# M217A.net
KiCad netlist of a schematic drawn in EAGLE
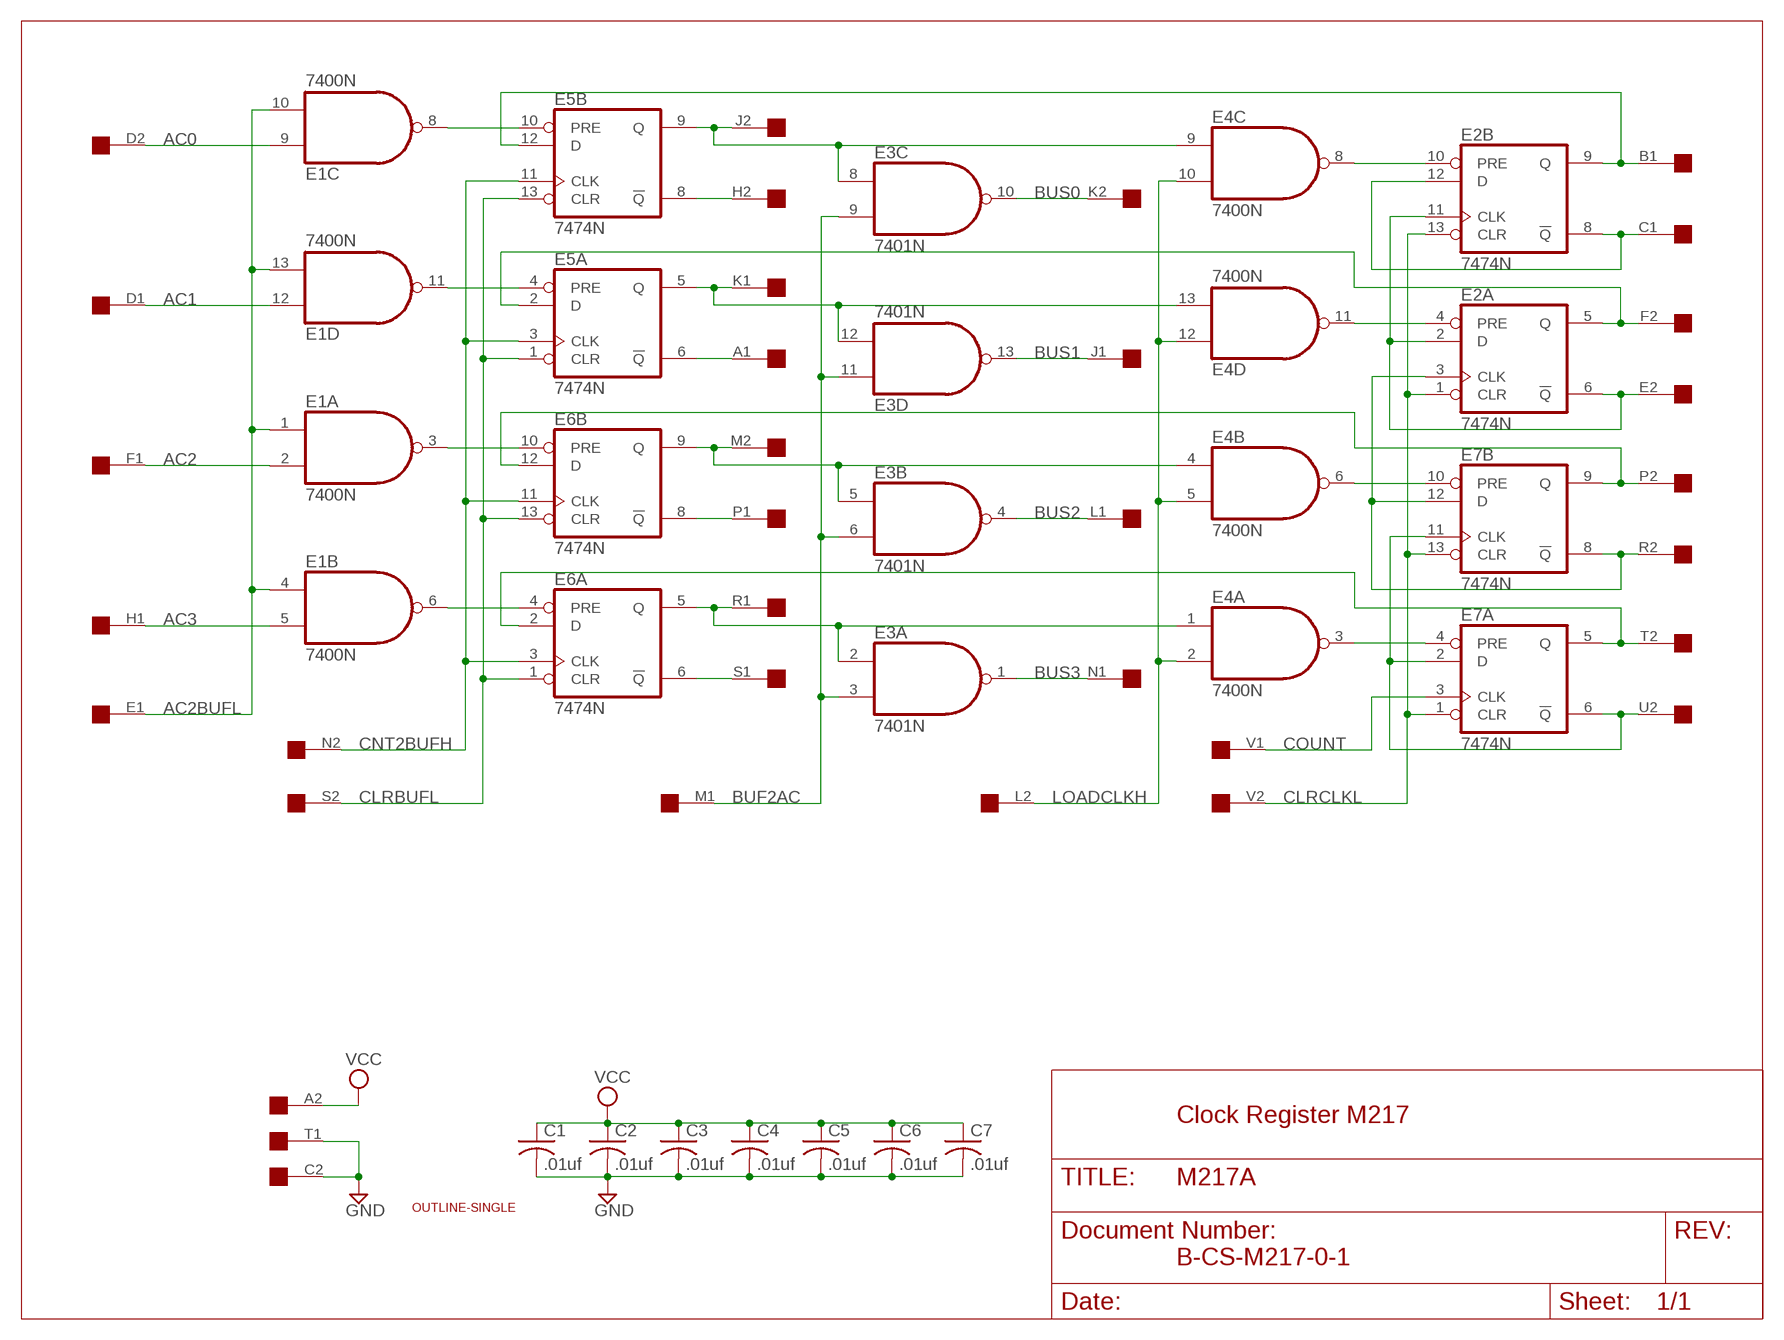
[diagram p0: schematic, sheet 1]

(export (version "E")
  (design (tool "Eeschema 10.0.6"))
  (components
    (comp (ref "C1")
      (value ".01uf")
      (footprint "eagle-import:C050-025X075")
      (libsource (lib "eagle-import") (part "C-US050-025X075"))
    )
    (comp (ref "C2")
      (value ".01uf")
      (footprint "eagle-import:C050-025X075")
      (libsource (lib "eagle-import") (part "C-US050-025X075"))
    )
    (comp (ref "C3")
      (value ".01uf")
      (footprint "eagle-import:C050-025X075")
      (libsource (lib "eagle-import") (part "C-US050-025X075"))
    )
    (comp (ref "C4")
      (value ".01uf")
      (footprint "eagle-import:C050-025X075")
      (libsource (lib "eagle-import") (part "C-US050-025X075"))
    )
    (comp (ref "C5")
      (value ".01uf")
      (footprint "eagle-import:C050-025X075")
      (libsource (lib "eagle-import") (part "C-US050-025X075"))
    )
    (comp (ref "C6")
      (value ".01uf")
      (footprint "eagle-import:C050-025X075")
      (libsource (lib "eagle-import") (part "C-US050-025X075"))
    )
    (comp (ref "C7")
      (value ".01uf")
      (footprint "eagle-import:C050-025X075")
      (libsource (lib "eagle-import") (part "C-US050-025X075"))
    )
    (comp (ref "E1")
      (value "7400N")
      (footprint "eagle-import:DIL14")
      (libsource (lib "eagle-import") (part "7400N"))
    )
    (comp (ref "E2")
      (value "7474N")
      (footprint "eagle-import:DIL14")
      (libsource (lib "eagle-import") (part "7474NS"))
    )
    (comp (ref "E3")
      (value "7401N")
      (footprint "eagle-import:DIL14")
      (libsource (lib "eagle-import") (part "7401NLS"))
    )
    (comp (ref "E4")
      (value "7400N")
      (footprint "eagle-import:DIL14")
      (libsource (lib "eagle-import") (part "7400N"))
    )
    (comp (ref "E5")
      (value "7474N")
      (footprint "eagle-import:DIL14")
      (libsource (lib "eagle-import") (part "7474NS"))
    )
    (comp (ref "E6")
      (value "7474N")
      (footprint "eagle-import:DIL14")
      (libsource (lib "eagle-import") (part "7474NS"))
    )
    (comp (ref "E7")
      (value "7474N")
      (footprint "eagle-import:DIL14")
      (libsource (lib "eagle-import") (part "7474NS"))
    )
    (comp (ref "U$1")
      (value "OUTLINE-SINGLE")
      (footprint "eagle-import:SINGLE")
      (libsource (lib "eagle-import") (part "OUTLINE-SINGLE"))
    )
    (comp (ref "U$4")
      (value "SINGLE")
      (footprint "eagle-import:EDGE-CON2")
      (libsource (lib "eagle-import") (part "SINGLE"))
    )
  )
  (nets
    (net (code "1") (name "/AC0") (class "Default")
      (node (ref "E1") (pin "9") (pinfunction "I0_9") (pintype "input"))
      (node (ref "U$4") (pin "D2") (pinfunction "1_D2") (pintype "bidirectional"))
    )
    (net (code "2") (name "/AC1") (class "Default")
      (node (ref "E1") (pin "12") (pinfunction "I0_12") (pintype "input"))
      (node (ref "U$4") (pin "D1") (pinfunction "1_D1") (pintype "bidirectional"))
    )
    (net (code "3") (name "/AC2") (class "Default")
      (node (ref "E1") (pin "2") (pinfunction "I1_2") (pintype "input"))
      (node (ref "U$4") (pin "F1") (pinfunction "1_F1") (pintype "bidirectional"))
    )
    (net (code "4") (name "/AC2BUFL") (class "Default")
      (node (ref "E1") (pin "1") (pinfunction "I0_1") (pintype "input"))
      (node (ref "E1") (pin "10") (pinfunction "I1_10") (pintype "input"))
      (node (ref "E1") (pin "13") (pinfunction "I1_13") (pintype "input"))
      (node (ref "E1") (pin "4") (pinfunction "I0_4") (pintype "input"))
      (node (ref "U$4") (pin "E1") (pinfunction "1_E1") (pintype "bidirectional"))
    )
    (net (code "5") (name "/AC3") (class "Default")
      (node (ref "E1") (pin "5") (pinfunction "I1_5") (pintype "input"))
      (node (ref "U$4") (pin "H1") (pinfunction "1_H1") (pintype "bidirectional"))
    )
    (net (code "6") (name "/BUF2AC") (class "Default")
      (node (ref "E3") (pin "11") (pinfunction "I0_11") (pintype "input"))
      (node (ref "E3") (pin "3") (pinfunction "I1_3") (pintype "input"))
      (node (ref "E3") (pin "6") (pinfunction "I1_6") (pintype "input"))
      (node (ref "E3") (pin "9") (pinfunction "I1_9") (pintype "input"))
      (node (ref "U$4") (pin "M1") (pinfunction "1_M1") (pintype "bidirectional"))
    )
    (net (code "7") (name "/BUS0") (class "Default")
      (node (ref "E3") (pin "10") (pinfunction "O_10") (pintype "open_collector"))
      (node (ref "U$4") (pin "K2") (pinfunction "1_K2") (pintype "bidirectional"))
    )
    (net (code "8") (name "/BUS1") (class "Default")
      (node (ref "E3") (pin "13") (pinfunction "O_13") (pintype "open_collector"))
      (node (ref "U$4") (pin "J1") (pinfunction "1_J1") (pintype "bidirectional"))
    )
    (net (code "9") (name "/BUS2") (class "Default")
      (node (ref "E3") (pin "4") (pinfunction "O_4") (pintype "open_collector"))
      (node (ref "U$4") (pin "L1") (pinfunction "1_L1") (pintype "bidirectional"))
    )
    (net (code "10") (name "/BUS3") (class "Default")
      (node (ref "E3") (pin "1") (pinfunction "O_1") (pintype "open_collector"))
      (node (ref "U$4") (pin "N1") (pinfunction "1_N1") (pintype "bidirectional"))
    )
    (net (code "11") (name "/CLRBUFL") (class "Default")
      (node (ref "E5") (pin "1") (pinfunction "CLR_1") (pintype "input"))
      (node (ref "E5") (pin "13") (pinfunction "CLR_13") (pintype "input"))
      (node (ref "E6") (pin "1") (pinfunction "CLR_1") (pintype "input"))
      (node (ref "E6") (pin "13") (pinfunction "CLR_13") (pintype "input"))
      (node (ref "U$4") (pin "S2") (pinfunction "1_S2") (pintype "bidirectional"))
    )
    (net (code "12") (name "/CLRCLKL") (class "Default")
      (node (ref "E2") (pin "1") (pinfunction "CLR_1") (pintype "input"))
      (node (ref "E2") (pin "13") (pinfunction "CLR_13") (pintype "input"))
      (node (ref "E7") (pin "1") (pinfunction "CLR_1") (pintype "input"))
      (node (ref "E7") (pin "13") (pinfunction "CLR_13") (pintype "input"))
      (node (ref "U$4") (pin "V2") (pinfunction "1_V2") (pintype "bidirectional"))
    )
    (net (code "13") (name "/CNT2BUFH") (class "Default")
      (node (ref "E5") (pin "11") (pinfunction "CLK_11") (pintype "input"))
      (node (ref "E5") (pin "3") (pinfunction "CLK_3") (pintype "input"))
      (node (ref "E6") (pin "11") (pinfunction "CLK_11") (pintype "input"))
      (node (ref "E6") (pin "3") (pinfunction "CLK_3") (pintype "input"))
      (node (ref "U$4") (pin "N2") (pinfunction "1_N2") (pintype "bidirectional"))
    )
    (net (code "14") (name "/COUNT") (class "Default")
      (node (ref "E7") (pin "3") (pinfunction "CLK_3") (pintype "input"))
      (node (ref "U$4") (pin "V1") (pinfunction "1_V1") (pintype "bidirectional"))
    )
    (net (code "15") (name "/LOADCLKH") (class "Default")
      (node (ref "E4") (pin "10") (pinfunction "I1_10") (pintype "input"))
      (node (ref "E4") (pin "12") (pinfunction "I0_12") (pintype "input"))
      (node (ref "E4") (pin "2") (pinfunction "I1_2") (pintype "input"))
      (node (ref "E4") (pin "5") (pinfunction "I1_5") (pintype "input"))
      (node (ref "U$4") (pin "L2") (pinfunction "1_L2") (pintype "bidirectional"))
    )
    (net (code "16") (name "GND") (class "Default")
      (node (ref "C1") (pin "2") (pinfunction "2_2") (pintype "passive"))
      (node (ref "C2") (pin "2") (pinfunction "2_2") (pintype "passive"))
      (node (ref "C3") (pin "2") (pinfunction "2_2") (pintype "passive"))
      (node (ref "C4") (pin "2") (pinfunction "2_2") (pintype "passive"))
      (node (ref "C5") (pin "2") (pinfunction "2_2") (pintype "passive"))
      (node (ref "C6") (pin "2") (pinfunction "2_2") (pintype "passive"))
      (node (ref "C7") (pin "2") (pinfunction "2_2") (pintype "passive"))
      (node (ref "U$4") (pin "C2") (pinfunction "1_C2") (pintype "bidirectional"))
      (node (ref "U$4") (pin "T1") (pinfunction "1_T1") (pintype "bidirectional"))
    )
    (net (code "17") (name "Net-(E1A-O)") (class "Default")
      (node (ref "E1") (pin "3") (pinfunction "O_3") (pintype "output"))
      (node (ref "E6") (pin "10") (pinfunction "PRE_10") (pintype "input"))
    )
    (net (code "18") (name "Net-(E1B-O)") (class "Default")
      (node (ref "E1") (pin "6") (pinfunction "O_6") (pintype "output"))
      (node (ref "E6") (pin "4") (pinfunction "PRE_4") (pintype "input"))
    )
    (net (code "19") (name "Net-(E1C-O)") (class "Default")
      (node (ref "E1") (pin "8") (pinfunction "O_8") (pintype "output"))
      (node (ref "E5") (pin "10") (pinfunction "PRE_10") (pintype "input"))
    )
    (net (code "20") (name "Net-(E1D-O)") (class "Default")
      (node (ref "E1") (pin "11") (pinfunction "O_11") (pintype "output"))
      (node (ref "E5") (pin "4") (pinfunction "PRE_4") (pintype "input"))
    )
    (net (code "21") (name "Net-(E2A-CLK)") (class "Default")
      (node (ref "E2") (pin "3") (pinfunction "CLK_3") (pintype "input"))
      (node (ref "E7") (pin "12") (pinfunction "D_12") (pintype "input"))
      (node (ref "E7") (pin "8") (pinfunction "~{Q}_8") (pintype "output"))
      (node (ref "U$4") (pin "R2") (pinfunction "1_R2") (pintype "bidirectional"))
    )
    (net (code "22") (name "Net-(E2A-D)") (class "Default")
      (node (ref "E2") (pin "11") (pinfunction "CLK_11") (pintype "input"))
      (node (ref "E2") (pin "2") (pinfunction "D_2") (pintype "input"))
      (node (ref "E2") (pin "6") (pinfunction "~{Q}_6") (pintype "output"))
      (node (ref "U$4") (pin "E2") (pinfunction "1_E2") (pintype "bidirectional"))
    )
    (net (code "23") (name "Net-(E2A-PRE)") (class "Default")
      (node (ref "E2") (pin "4") (pinfunction "PRE_4") (pintype "input"))
      (node (ref "E4") (pin "11") (pinfunction "O_11") (pintype "output"))
    )
    (net (code "24") (name "Net-(E2A-Q)") (class "Default")
      (node (ref "E2") (pin "5") (pinfunction "Q_5") (pintype "output"))
      (node (ref "E5") (pin "2") (pinfunction "D_2") (pintype "input"))
      (node (ref "U$4") (pin "F2") (pinfunction "1_F2") (pintype "bidirectional"))
    )
    (net (code "25") (name "Net-(E2B-D)") (class "Default")
      (node (ref "E2") (pin "12") (pinfunction "D_12") (pintype "input"))
      (node (ref "E2") (pin "8") (pinfunction "~{Q}_8") (pintype "output"))
      (node (ref "U$4") (pin "C1") (pinfunction "1_C1") (pintype "bidirectional"))
    )
    (net (code "26") (name "Net-(E2B-PRE)") (class "Default")
      (node (ref "E2") (pin "10") (pinfunction "PRE_10") (pintype "input"))
      (node (ref "E4") (pin "8") (pinfunction "O_8") (pintype "output"))
    )
    (net (code "27") (name "Net-(E2B-Q)") (class "Default")
      (node (ref "E2") (pin "9") (pinfunction "Q_9") (pintype "output"))
      (node (ref "E5") (pin "12") (pinfunction "D_12") (pintype "input"))
      (node (ref "U$4") (pin "B1") (pinfunction "1_B1") (pintype "bidirectional"))
    )
    (net (code "28") (name "Net-(E3A-I0)") (class "Default")
      (node (ref "E3") (pin "2") (pinfunction "I0_2") (pintype "input"))
      (node (ref "E4") (pin "1") (pinfunction "I0_1") (pintype "input"))
      (node (ref "E6") (pin "5") (pinfunction "Q_5") (pintype "output"))
      (node (ref "U$4") (pin "R1") (pinfunction "1_R1") (pintype "bidirectional"))
    )
    (net (code "29") (name "Net-(E3B-I0)") (class "Default")
      (node (ref "E3") (pin "5") (pinfunction "I0_5") (pintype "input"))
      (node (ref "E4") (pin "4") (pinfunction "I0_4") (pintype "input"))
      (node (ref "E6") (pin "9") (pinfunction "Q_9") (pintype "output"))
      (node (ref "U$4") (pin "M2") (pinfunction "1_M2") (pintype "bidirectional"))
    )
    (net (code "30") (name "Net-(E3C-I0)") (class "Default")
      (node (ref "E3") (pin "8") (pinfunction "I0_8") (pintype "input"))
      (node (ref "E4") (pin "9") (pinfunction "I0_9") (pintype "input"))
      (node (ref "E5") (pin "9") (pinfunction "Q_9") (pintype "output"))
      (node (ref "U$4") (pin "J2") (pinfunction "1_J2") (pintype "bidirectional"))
    )
    (net (code "31") (name "Net-(E3D-I1)") (class "Default")
      (node (ref "E3") (pin "12") (pinfunction "I1_12") (pintype "input"))
      (node (ref "E4") (pin "13") (pinfunction "I1_13") (pintype "input"))
      (node (ref "E5") (pin "5") (pinfunction "Q_5") (pintype "output"))
      (node (ref "U$4") (pin "K1") (pinfunction "1_K1") (pintype "bidirectional"))
    )
    (net (code "32") (name "Net-(E4A-O)") (class "Default")
      (node (ref "E4") (pin "3") (pinfunction "O_3") (pintype "output"))
      (node (ref "E7") (pin "4") (pinfunction "PRE_4") (pintype "input"))
    )
    (net (code "33") (name "Net-(E4B-O)") (class "Default")
      (node (ref "E4") (pin "6") (pinfunction "O_6") (pintype "output"))
      (node (ref "E7") (pin "10") (pinfunction "PRE_10") (pintype "input"))
    )
    (net (code "34") (name "Net-(E5A-~{Q})") (class "Default")
      (node (ref "E5") (pin "6") (pinfunction "~{Q}_6") (pintype "output"))
      (node (ref "U$4") (pin "A1") (pinfunction "1_A1") (pintype "bidirectional"))
    )
    (net (code "35") (name "Net-(E5B-~{Q})") (class "Default")
      (node (ref "E5") (pin "8") (pinfunction "~{Q}_8") (pintype "output"))
      (node (ref "U$4") (pin "H2") (pinfunction "1_H2") (pintype "bidirectional"))
    )
    (net (code "36") (name "Net-(E6A-D)") (class "Default")
      (node (ref "E6") (pin "2") (pinfunction "D_2") (pintype "input"))
      (node (ref "E7") (pin "5") (pinfunction "Q_5") (pintype "output"))
      (node (ref "U$4") (pin "T2") (pinfunction "1_T2") (pintype "bidirectional"))
    )
    (net (code "37") (name "Net-(E6A-~{Q})") (class "Default")
      (node (ref "E6") (pin "6") (pinfunction "~{Q}_6") (pintype "output"))
      (node (ref "U$4") (pin "S1") (pinfunction "1_S1") (pintype "bidirectional"))
    )
    (net (code "38") (name "Net-(E6B-D)") (class "Default")
      (node (ref "E6") (pin "12") (pinfunction "D_12") (pintype "input"))
      (node (ref "E7") (pin "9") (pinfunction "Q_9") (pintype "output"))
      (node (ref "U$4") (pin "P2") (pinfunction "1_P2") (pintype "bidirectional"))
    )
    (net (code "39") (name "Net-(E6B-~{Q})") (class "Default")
      (node (ref "E6") (pin "8") (pinfunction "~{Q}_8") (pintype "output"))
      (node (ref "U$4") (pin "P1") (pinfunction "1_P1") (pintype "bidirectional"))
    )
    (net (code "40") (name "Net-(E7A-D)") (class "Default")
      (node (ref "E7") (pin "11") (pinfunction "CLK_11") (pintype "input"))
      (node (ref "E7") (pin "2") (pinfunction "D_2") (pintype "input"))
      (node (ref "E7") (pin "6") (pinfunction "~{Q}_6") (pintype "output"))
      (node (ref "U$4") (pin "U2") (pinfunction "1_U2") (pintype "bidirectional"))
    )
    (net (code "41") (name "VCC") (class "Default")
      (node (ref "C1") (pin "1") (pinfunction "1_1") (pintype "passive"))
      (node (ref "C2") (pin "1") (pinfunction "1_1") (pintype "passive"))
      (node (ref "C3") (pin "1") (pinfunction "1_1") (pintype "passive"))
      (node (ref "C4") (pin "1") (pinfunction "1_1") (pintype "passive"))
      (node (ref "C5") (pin "1") (pinfunction "1_1") (pintype "passive"))
      (node (ref "C6") (pin "1") (pinfunction "1_1") (pintype "passive"))
      (node (ref "C7") (pin "1") (pinfunction "1_1") (pintype "passive"))
      (node (ref "U$4") (pin "A2") (pinfunction "1_A2") (pintype "bidirectional"))
    )
  )
)
